# IPSv2_1.net
KiCad netlist of a schematic drawn in EAGLE
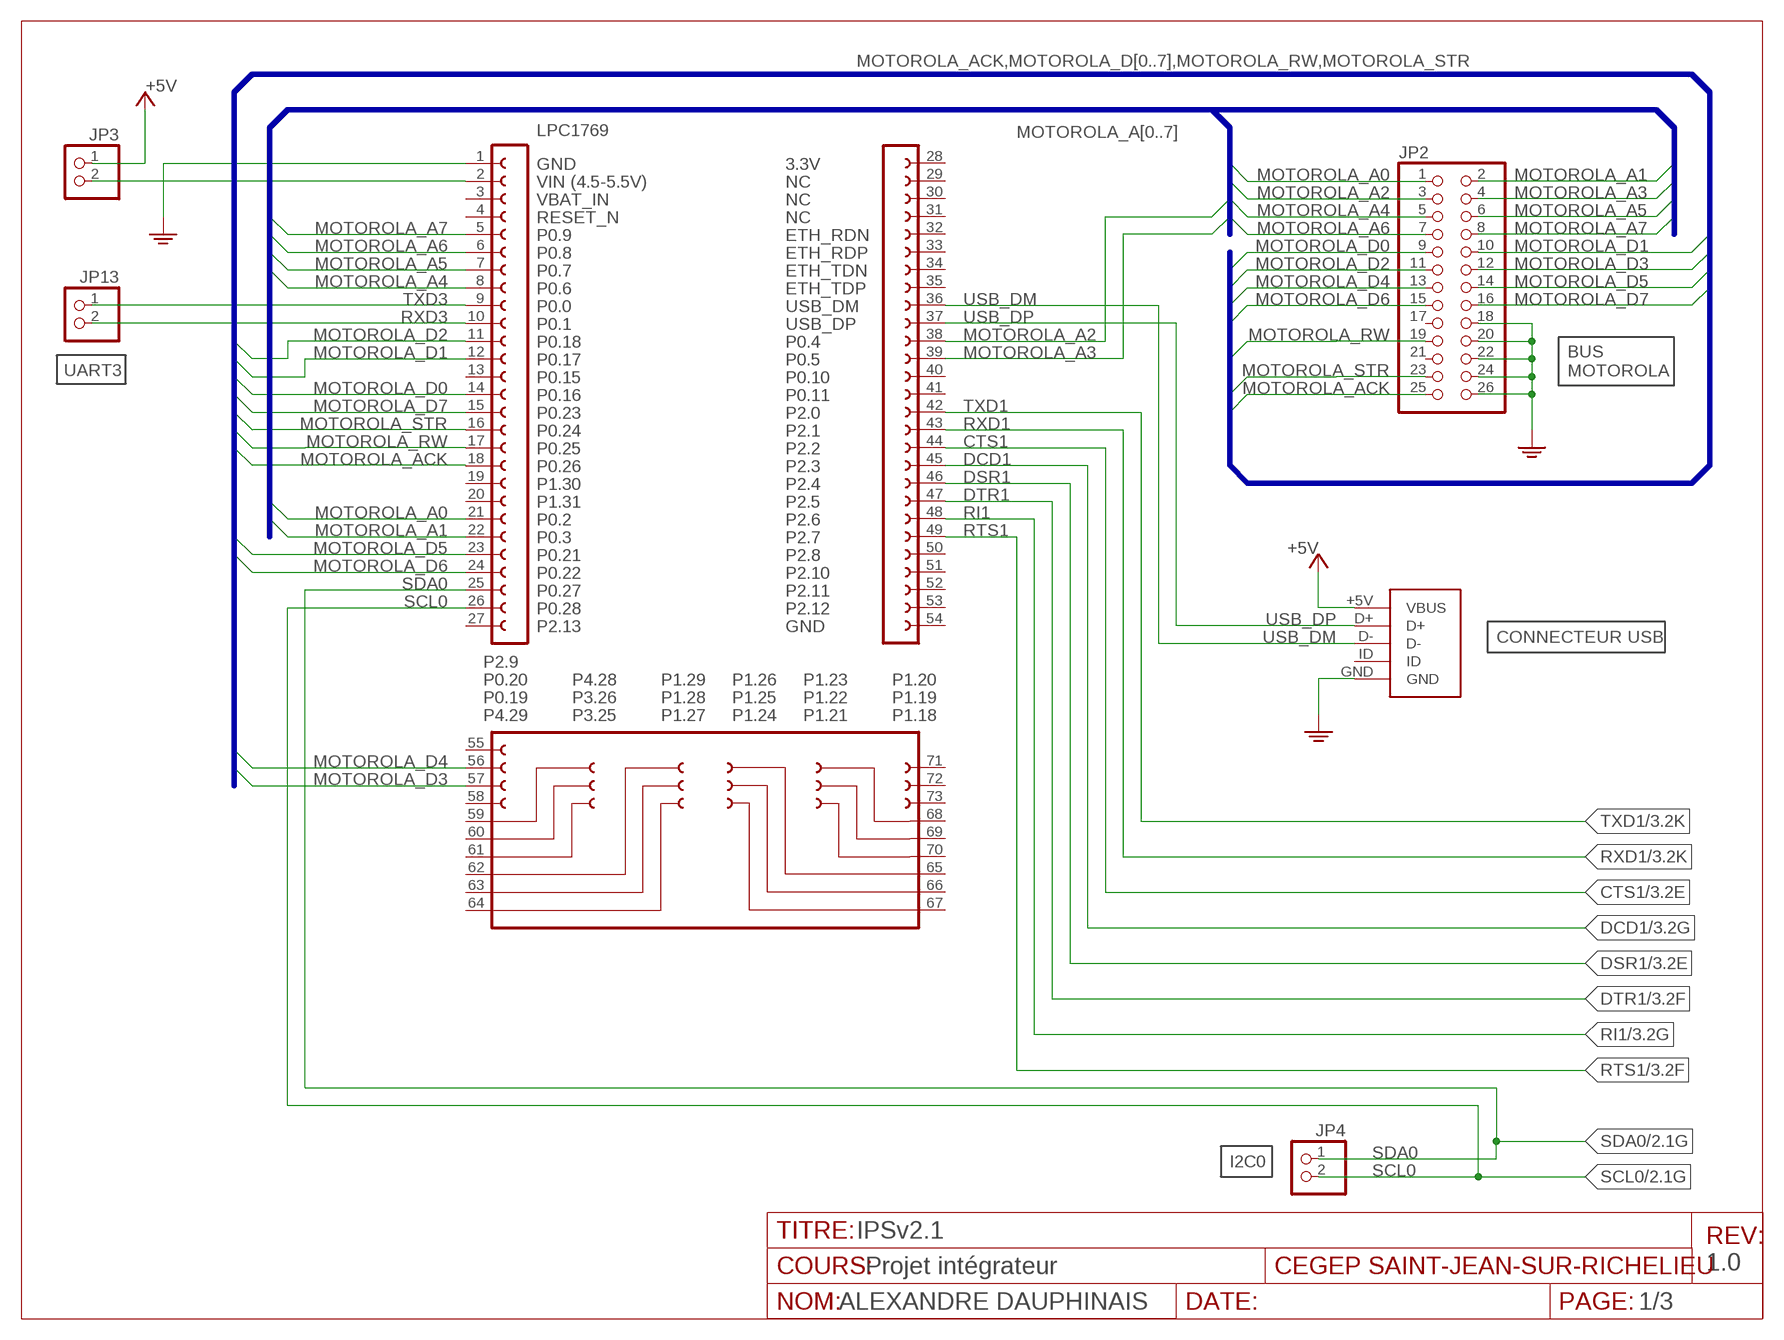
[diagram p0: schematic, sheet 1]
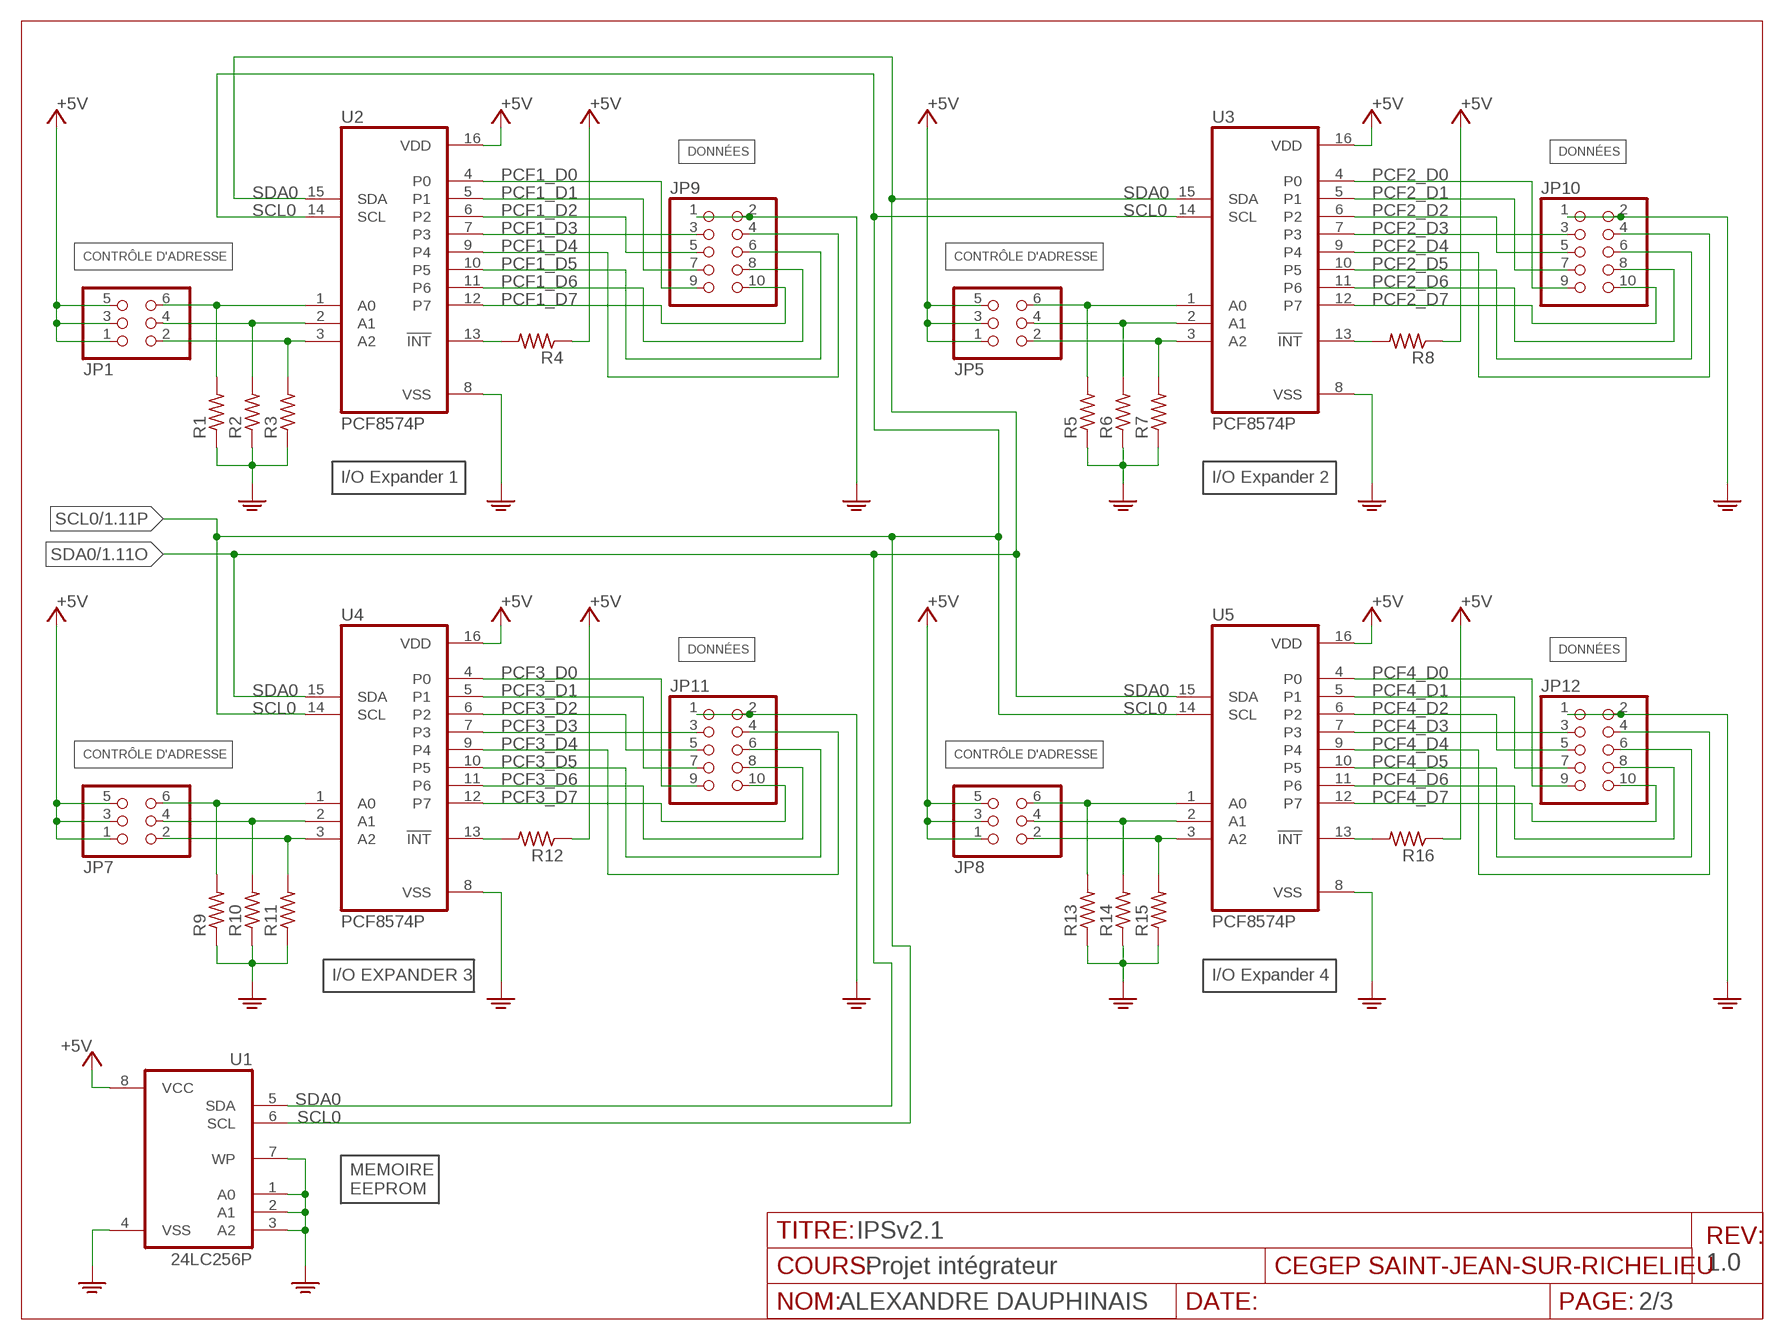
[diagram p1: schematic, sheet 2]
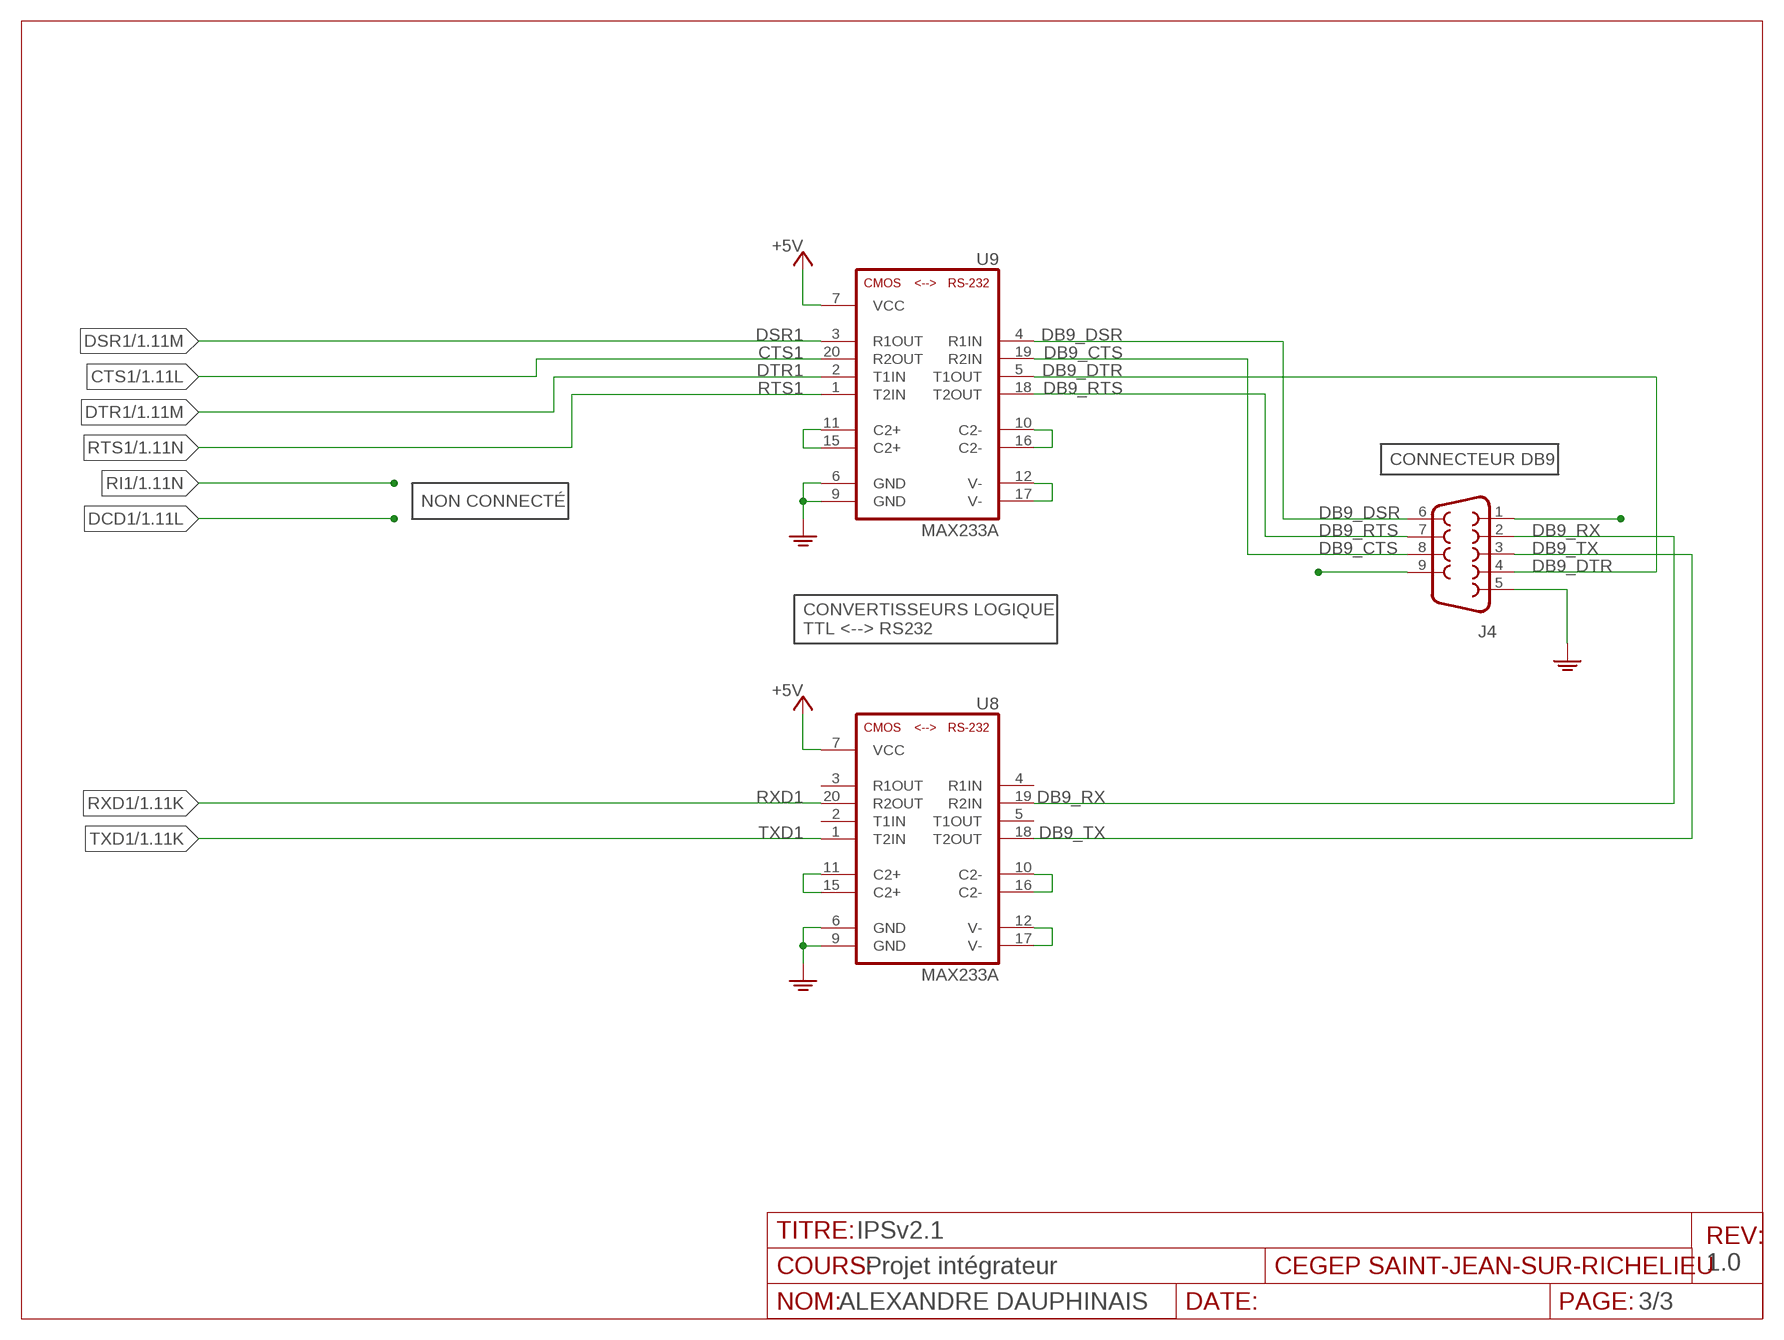
[diagram p2: schematic, sheet 3]

(export (version "E")
  (design (tool "Eeschema 10.0.6"))
  (components
    (comp (ref "J4")
      (value "DB9FEMALE")
      (footprint "eagle-import:DB9")
      (libsource (lib "eagle-import") (part "DB9FEMALE"))
    )
    (comp (ref "U8")
      (value "MAX233A")
      (footprint "eagle-import:DIP20")
      (libsource (lib "eagle-import") (part "MAX233ACPP"))
    )
    (comp (ref "U9")
      (value "MAX233A")
      (footprint "eagle-import:DIP20")
      (libsource (lib "eagle-import") (part "MAX233ACPP"))
    )
    (comp (ref "JP2")
      (value "PINHD-2X13")
      (footprint "eagle-import:2X13")
      (libsource (lib "eagle-import") (part "PINHD-2X13"))
    )
    (comp (ref "JP3")
      (value "PINHD-1X2")
      (footprint "eagle-import:1X02")
      (libsource (lib "eagle-import") (part "PINHD-1X2"))
    )
    (comp (ref "JP4")
      (value "PINHD-1X2")
      (footprint "eagle-import:1X02")
      (libsource (lib "eagle-import") (part "PINHD-1X2"))
    )
    (comp (ref "JP13")
      (value "PINHD-1X2")
      (footprint "eagle-import:1X02")
      (libsource (lib "eagle-import") (part "PINHD-1X2"))
    )
    (comp (ref "LPC1769")
      (value "LPCXPRESSO_LPC1769")
      (footprint "eagle-import:LPCXPRESSO_LPC1769")
      (libsource (lib "eagle-import") (part "LPCXPRESSO_LPC1769"))
    )
    (comp (ref "U$2")
      (value "USB-MICRO-BREAKOUT")
      (footprint "eagle-import:USB-MICRO-BREAKOUT")
      (libsource (lib "eagle-import") (part "USB-MICRO-BREAKOUT"))
    )
    (comp (ref "JP1")
      (value "PINHD-2X3")
      (footprint "eagle-import:2X03")
      (libsource (lib "eagle-import") (part "PINHD-2X3"))
    )
    (comp (ref "JP5")
      (value "PINHD-2X3")
      (footprint "eagle-import:2X03")
      (libsource (lib "eagle-import") (part "PINHD-2X3"))
    )
    (comp (ref "JP7")
      (value "PINHD-2X3")
      (footprint "eagle-import:2X03")
      (libsource (lib "eagle-import") (part "PINHD-2X3"))
    )
    (comp (ref "JP8")
      (value "PINHD-2X3")
      (footprint "eagle-import:2X03")
      (libsource (lib "eagle-import") (part "PINHD-2X3"))
    )
    (comp (ref "JP9")
      (value "PINHD-2X5")
      (footprint "eagle-import:2X05")
      (libsource (lib "eagle-import") (part "PINHD-2X5"))
    )
    (comp (ref "JP10")
      (value "PINHD-2X5")
      (footprint "eagle-import:2X05")
      (libsource (lib "eagle-import") (part "PINHD-2X5"))
    )
    (comp (ref "JP11")
      (value "PINHD-2X5")
      (footprint "eagle-import:2X05")
      (libsource (lib "eagle-import") (part "PINHD-2X5"))
    )
    (comp (ref "JP12")
      (value "PINHD-2X5")
      (footprint "eagle-import:2X05")
      (libsource (lib "eagle-import") (part "PINHD-2X5"))
    )
    (comp (ref "R1")
      (value "R-US_M1206")
      (footprint "eagle-import:M1206")
      (libsource (lib "eagle-import") (part "R-US_M1206"))
    )
    (comp (ref "R2")
      (value "R-US_M1206")
      (footprint "eagle-import:M1206")
      (libsource (lib "eagle-import") (part "R-US_M1206"))
    )
    (comp (ref "R3")
      (value "R-US_M1206")
      (footprint "eagle-import:M1206")
      (libsource (lib "eagle-import") (part "R-US_M1206"))
    )
    (comp (ref "R4")
      (value "R-US_M1206")
      (footprint "eagle-import:M1206")
      (libsource (lib "eagle-import") (part "R-US_M1206"))
    )
    (comp (ref "R5")
      (value "R-US_M1206")
      (footprint "eagle-import:M1206")
      (libsource (lib "eagle-import") (part "R-US_M1206"))
    )
    (comp (ref "R6")
      (value "R-US_M1206")
      (footprint "eagle-import:M1206")
      (libsource (lib "eagle-import") (part "R-US_M1206"))
    )
    (comp (ref "R7")
      (value "R-US_M1206")
      (footprint "eagle-import:M1206")
      (libsource (lib "eagle-import") (part "R-US_M1206"))
    )
    (comp (ref "R8")
      (value "R-US_M1206")
      (footprint "eagle-import:M1206")
      (libsource (lib "eagle-import") (part "R-US_M1206"))
    )
    (comp (ref "R9")
      (value "R-US_M1206")
      (footprint "eagle-import:M1206")
      (libsource (lib "eagle-import") (part "R-US_M1206"))
    )
    (comp (ref "R10")
      (value "R-US_M1206")
      (footprint "eagle-import:M1206")
      (libsource (lib "eagle-import") (part "R-US_M1206"))
    )
    (comp (ref "R11")
      (value "R-US_M1206")
      (footprint "eagle-import:M1206")
      (libsource (lib "eagle-import") (part "R-US_M1206"))
    )
    (comp (ref "R12")
      (value "R-US_M1206")
      (footprint "eagle-import:M1206")
      (libsource (lib "eagle-import") (part "R-US_M1206"))
    )
    (comp (ref "R13")
      (value "R-US_M1206")
      (footprint "eagle-import:M1206")
      (libsource (lib "eagle-import") (part "R-US_M1206"))
    )
    (comp (ref "R14")
      (value "R-US_M1206")
      (footprint "eagle-import:M1206")
      (libsource (lib "eagle-import") (part "R-US_M1206"))
    )
    (comp (ref "R15")
      (value "R-US_M1206")
      (footprint "eagle-import:M1206")
      (libsource (lib "eagle-import") (part "R-US_M1206"))
    )
    (comp (ref "R16")
      (value "R-US_M1206")
      (footprint "eagle-import:M1206")
      (libsource (lib "eagle-import") (part "R-US_M1206"))
    )
    (comp (ref "U1")
      (value "24LC256P")
      (footprint "eagle-import:DIP08")
      (libsource (lib "eagle-import") (part "24LC256P"))
    )
    (comp (ref "U2")
      (value "PCF8574P")
      (footprint "eagle-import:DIP16")
      (libsource (lib "eagle-import") (part "PCF8574P"))
    )
    (comp (ref "U3")
      (value "PCF8574P")
      (footprint "eagle-import:DIP16")
      (libsource (lib "eagle-import") (part "PCF8574P"))
    )
    (comp (ref "U4")
      (value "PCF8574P")
      (footprint "eagle-import:DIP16")
      (libsource (lib "eagle-import") (part "PCF8574P"))
    )
    (comp (ref "U5")
      (value "PCF8574P")
      (footprint "eagle-import:DIP16")
      (libsource (lib "eagle-import") (part "PCF8574P"))
    )
  )
  (nets
    (net (code "1") (name "+5V") (class "Default")
      (node (ref "JP1") (pin "1") (pinfunction "1_1") (pintype "passive"))
      (node (ref "JP1") (pin "3") (pinfunction "3_3") (pintype "passive"))
      (node (ref "JP1") (pin "5") (pinfunction "5_5") (pintype "passive"))
      (node (ref "JP3") (pin "1") (pinfunction "1_1") (pintype "passive"))
      (node (ref "JP5") (pin "1") (pinfunction "1_1") (pintype "passive"))
      (node (ref "JP5") (pin "3") (pinfunction "3_3") (pintype "passive"))
      (node (ref "JP5") (pin "5") (pinfunction "5_5") (pintype "passive"))
      (node (ref "JP7") (pin "1") (pinfunction "1_1") (pintype "passive"))
      (node (ref "JP7") (pin "3") (pinfunction "3_3") (pintype "passive"))
      (node (ref "JP7") (pin "5") (pinfunction "5_5") (pintype "passive"))
      (node (ref "JP8") (pin "1") (pinfunction "1_1") (pintype "passive"))
      (node (ref "JP8") (pin "3") (pinfunction "3_3") (pintype "passive"))
      (node (ref "JP8") (pin "5") (pinfunction "5_5") (pintype "passive"))
      (node (ref "R12") (pin "1") (pinfunction "1_1") (pintype "passive"))
      (node (ref "R16") (pin "1") (pinfunction "1_1") (pintype "passive"))
      (node (ref "R4") (pin "1") (pinfunction "1_1") (pintype "passive"))
      (node (ref "R8") (pin "1") (pinfunction "1_1") (pintype "passive"))
      (node (ref "U$2") (pin "+5V") (pinfunction "VBUS_+5V") (pintype "power_in"))
      (node (ref "U1") (pin "8") (pinfunction "VCC_8") (pintype "power_in"))
      (node (ref "U2") (pin "16") (pinfunction "VDD_16") (pintype "power_in"))
      (node (ref "U3") (pin "16") (pinfunction "VDD_16") (pintype "power_in"))
      (node (ref "U4") (pin "16") (pinfunction "VDD_16") (pintype "power_in"))
      (node (ref "U5") (pin "16") (pinfunction "VDD_16") (pintype "power_in"))
      (node (ref "U8") (pin "7") (pinfunction "VCC_7") (pintype "power_in"))
      (node (ref "U9") (pin "7") (pinfunction "VCC_7") (pintype "power_in"))
    )
    (net (code "4") (name "CTS1") (class "Default")
      (node (ref "LPC1769") (pin "44") (pinfunction "44_44") (pintype "passive"))
      (node (ref "U9") (pin "20") (pinfunction "R2OUT_20") (pintype "output"))
    )
    (net (code "5") (name "DB9_CTS") (class "Default")
      (node (ref "J4") (pin "8") (pinfunction "8_8") (pintype "passive"))
      (node (ref "U9") (pin "19") (pinfunction "R2IN_19") (pintype "input"))
    )
    (net (code "6") (name "DB9_DSR") (class "Default")
      (node (ref "J4") (pin "6") (pinfunction "6_6") (pintype "passive"))
      (node (ref "U9") (pin "4") (pinfunction "R1IN_4") (pintype "input"))
    )
    (net (code "7") (name "DB9_DTR") (class "Default")
      (node (ref "J4") (pin "4") (pinfunction "4_4") (pintype "passive"))
      (node (ref "U9") (pin "5") (pinfunction "T1OUT_5") (pintype "output"))
    )
    (net (code "8") (name "DB9_RTS") (class "Default")
      (node (ref "J4") (pin "7") (pinfunction "7_7") (pintype "passive"))
      (node (ref "U9") (pin "18") (pinfunction "T2OUT_18") (pintype "output"))
    )
    (net (code "9") (name "DB9_RX") (class "Default")
      (node (ref "J4") (pin "2") (pinfunction "2_2") (pintype "passive"))
      (node (ref "U8") (pin "19") (pinfunction "R2IN_19") (pintype "input"))
    )
    (net (code "10") (name "DB9_TX") (class "Default")
      (node (ref "J4") (pin "3") (pinfunction "3_3") (pintype "passive"))
      (node (ref "U8") (pin "18") (pinfunction "T2OUT_18") (pintype "output"))
    )
    (net (code "11") (name "DCD1") (class "Default")
      (node (ref "LPC1769") (pin "45") (pinfunction "45_45") (pintype "passive"))
    )
    (net (code "12") (name "DSR1") (class "Default")
      (node (ref "LPC1769") (pin "46") (pinfunction "46_46") (pintype "passive"))
      (node (ref "U9") (pin "3") (pinfunction "R1OUT_3") (pintype "output"))
    )
    (net (code "13") (name "DTR1") (class "Default")
      (node (ref "LPC1769") (pin "47") (pinfunction "47_47") (pintype "passive"))
      (node (ref "U9") (pin "2") (pinfunction "T1IN_2") (pintype "input"))
    )
    (net (code "14") (name "GND") (class "Default")
      (node (ref "J4") (pin "5") (pinfunction "5_5") (pintype "passive"))
      (node (ref "JP10") (pin "1") (pinfunction "1_1") (pintype "passive"))
      (node (ref "JP10") (pin "2") (pinfunction "2_2") (pintype "passive"))
      (node (ref "JP11") (pin "1") (pinfunction "1_1") (pintype "passive"))
      (node (ref "JP11") (pin "2") (pinfunction "2_2") (pintype "passive"))
      (node (ref "JP12") (pin "1") (pinfunction "1_1") (pintype "passive"))
      (node (ref "JP12") (pin "2") (pinfunction "2_2") (pintype "passive"))
      (node (ref "JP2") (pin "18") (pinfunction "18_18") (pintype "passive"))
      (node (ref "JP2") (pin "20") (pinfunction "20_20") (pintype "passive"))
      (node (ref "JP2") (pin "22") (pinfunction "22_22") (pintype "passive"))
      (node (ref "JP2") (pin "24") (pinfunction "24_24") (pintype "passive"))
      (node (ref "JP2") (pin "26") (pinfunction "26_26") (pintype "passive"))
      (node (ref "JP9") (pin "1") (pinfunction "1_1") (pintype "passive"))
      (node (ref "JP9") (pin "2") (pinfunction "2_2") (pintype "passive"))
      (node (ref "LPC1769") (pin "1") (pinfunction "1_1") (pintype "passive"))
      (node (ref "R1") (pin "1") (pinfunction "1_1") (pintype "passive"))
      (node (ref "R10") (pin "1") (pinfunction "1_1") (pintype "passive"))
      (node (ref "R11") (pin "1") (pinfunction "1_1") (pintype "passive"))
      (node (ref "R13") (pin "1") (pinfunction "1_1") (pintype "passive"))
      (node (ref "R14") (pin "1") (pinfunction "1_1") (pintype "passive"))
      (node (ref "R15") (pin "1") (pinfunction "1_1") (pintype "passive"))
      (node (ref "R2") (pin "1") (pinfunction "1_1") (pintype "passive"))
      (node (ref "R3") (pin "1") (pinfunction "1_1") (pintype "passive"))
      (node (ref "R5") (pin "1") (pinfunction "1_1") (pintype "passive"))
      (node (ref "R6") (pin "1") (pinfunction "1_1") (pintype "passive"))
      (node (ref "R7") (pin "1") (pinfunction "1_1") (pintype "passive"))
      (node (ref "R9") (pin "1") (pinfunction "1_1") (pintype "passive"))
      (node (ref "U$2") (pin "GND") (pinfunction "GND_GND") (pintype "power_in"))
      (node (ref "U1") (pin "1") (pinfunction "A0_1") (pintype "input"))
      (node (ref "U1") (pin "2") (pinfunction "A1_2") (pintype "input"))
      (node (ref "U1") (pin "3") (pinfunction "A2_3") (pintype "input"))
      (node (ref "U1") (pin "4") (pinfunction "VSS_4") (pintype "power_in"))
      (node (ref "U1") (pin "7") (pinfunction "WP_7") (pintype "input"))
      (node (ref "U2") (pin "8") (pinfunction "VSS_8") (pintype "power_in"))
      (node (ref "U3") (pin "8") (pinfunction "VSS_8") (pintype "power_in"))
      (node (ref "U4") (pin "8") (pinfunction "VSS_8") (pintype "power_in"))
      (node (ref "U5") (pin "8") (pinfunction "VSS_8") (pintype "power_in"))
      (node (ref "U8") (pin "6") (pinfunction "GND_6") (pintype "power_in"))
      (node (ref "U8") (pin "9") (pinfunction "GND_9") (pintype "power_in"))
      (node (ref "U9") (pin "6") (pinfunction "GND_6") (pintype "power_in"))
      (node (ref "U9") (pin "9") (pinfunction "GND_9") (pintype "power_in"))
    )
    (net (code "15") (name "MOTOROLA_A0") (class "Default")
      (node (ref "JP2") (pin "1") (pinfunction "1_1") (pintype "passive"))
      (node (ref "LPC1769") (pin "21") (pinfunction "21_21") (pintype "passive"))
    )
    (net (code "16") (name "MOTOROLA_A1") (class "Default")
      (node (ref "JP2") (pin "2") (pinfunction "2_2") (pintype "passive"))
      (node (ref "LPC1769") (pin "22") (pinfunction "22_22") (pintype "passive"))
    )
    (net (code "17") (name "MOTOROLA_A2") (class "Default")
      (node (ref "JP2") (pin "3") (pinfunction "3_3") (pintype "passive"))
      (node (ref "LPC1769") (pin "38") (pinfunction "38_38") (pintype "passive"))
    )
    (net (code "18") (name "MOTOROLA_A3") (class "Default")
      (node (ref "JP2") (pin "4") (pinfunction "4_4") (pintype "passive"))
      (node (ref "LPC1769") (pin "39") (pinfunction "39_39") (pintype "passive"))
    )
    (net (code "19") (name "MOTOROLA_A4") (class "Default")
      (node (ref "JP2") (pin "5") (pinfunction "5_5") (pintype "passive"))
      (node (ref "LPC1769") (pin "8") (pinfunction "8_8") (pintype "passive"))
    )
    (net (code "20") (name "MOTOROLA_A5") (class "Default")
      (node (ref "JP2") (pin "6") (pinfunction "6_6") (pintype "passive"))
      (node (ref "LPC1769") (pin "7") (pinfunction "7_7") (pintype "passive"))
    )
    (net (code "21") (name "MOTOROLA_A6") (class "Default")
      (node (ref "JP2") (pin "7") (pinfunction "7_7") (pintype "passive"))
      (node (ref "LPC1769") (pin "6") (pinfunction "6_6") (pintype "passive"))
    )
    (net (code "22") (name "MOTOROLA_A7") (class "Default")
      (node (ref "JP2") (pin "8") (pinfunction "8_8") (pintype "passive"))
      (node (ref "LPC1769") (pin "5") (pinfunction "5_5") (pintype "passive"))
    )
    (net (code "23") (name "MOTOROLA_ACK") (class "Default")
      (node (ref "JP2") (pin "25") (pinfunction "25_25") (pintype "passive"))
      (node (ref "LPC1769") (pin "18") (pinfunction "18_18") (pintype "passive"))
    )
    (net (code "24") (name "MOTOROLA_D0") (class "Default")
      (node (ref "JP2") (pin "9") (pinfunction "9_9") (pintype "passive"))
      (node (ref "LPC1769") (pin "14") (pinfunction "14_14") (pintype "passive"))
    )
    (net (code "25") (name "MOTOROLA_D1") (class "Default")
      (node (ref "JP2") (pin "10") (pinfunction "10_10") (pintype "passive"))
      (node (ref "LPC1769") (pin "12") (pinfunction "12_12") (pintype "passive"))
    )
    (net (code "26") (name "MOTOROLA_D2") (class "Default")
      (node (ref "JP2") (pin "11") (pinfunction "11_11") (pintype "passive"))
      (node (ref "LPC1769") (pin "11") (pinfunction "11_11") (pintype "passive"))
    )
    (net (code "27") (name "MOTOROLA_D3") (class "Default")
      (node (ref "JP2") (pin "12") (pinfunction "12_12") (pintype "passive"))
      (node (ref "LPC1769") (pin "57") (pinfunction "57_57") (pintype "passive"))
    )
    (net (code "28") (name "MOTOROLA_D4") (class "Default")
      (node (ref "JP2") (pin "13") (pinfunction "13_13") (pintype "passive"))
      (node (ref "LPC1769") (pin "56") (pinfunction "56_56") (pintype "passive"))
    )
    (net (code "29") (name "MOTOROLA_D5") (class "Default")
      (node (ref "JP2") (pin "14") (pinfunction "14_14") (pintype "passive"))
      (node (ref "LPC1769") (pin "23") (pinfunction "23_23") (pintype "passive"))
    )
    (net (code "30") (name "MOTOROLA_D6") (class "Default")
      (node (ref "JP2") (pin "15") (pinfunction "15_15") (pintype "passive"))
      (node (ref "LPC1769") (pin "24") (pinfunction "24_24") (pintype "passive"))
    )
    (net (code "31") (name "MOTOROLA_D7") (class "Default")
      (node (ref "JP2") (pin "16") (pinfunction "16_16") (pintype "passive"))
      (node (ref "LPC1769") (pin "15") (pinfunction "15_15") (pintype "passive"))
    )
    (net (code "32") (name "MOTOROLA_RW") (class "Default")
      (node (ref "JP2") (pin "19") (pinfunction "19_19") (pintype "passive"))
      (node (ref "LPC1769") (pin "17") (pinfunction "17_17") (pintype "passive"))
    )
    (net (code "33") (name "MOTOROLA_STR") (class "Default")
      (node (ref "JP2") (pin "23") (pinfunction "23_23") (pintype "passive"))
      (node (ref "LPC1769") (pin "16") (pinfunction "16_16") (pintype "passive"))
    )
    (net (code "34") (name "Net-(JP3-Pad2)") (class "Default")
      (node (ref "JP3") (pin "2") (pinfunction "2_2") (pintype "passive"))
      (node (ref "LPC1769") (pin "2") (pinfunction "2_2") (pintype "passive"))
    )
    (net (code "35") (name "Net-(U2-A0)") (class "Default")
      (node (ref "JP1") (pin "6") (pinfunction "6_6") (pintype "passive"))
      (node (ref "R1") (pin "2") (pinfunction "2_2") (pintype "passive"))
      (node (ref "U2") (pin "1") (pinfunction "A0_1") (pintype "input"))
    )
    (net (code "36") (name "Net-(U2-A1)") (class "Default")
      (node (ref "JP1") (pin "4") (pinfunction "4_4") (pintype "passive"))
      (node (ref "R2") (pin "2") (pinfunction "2_2") (pintype "passive"))
      (node (ref "U2") (pin "2") (pinfunction "A1_2") (pintype "input"))
    )
    (net (code "37") (name "Net-(U2-A2)") (class "Default")
      (node (ref "JP1") (pin "2") (pinfunction "2_2") (pintype "passive"))
      (node (ref "R3") (pin "2") (pinfunction "2_2") (pintype "passive"))
      (node (ref "U2") (pin "3") (pinfunction "A2_3") (pintype "input"))
    )
    (net (code "38") (name "Net-(U2-~{INT})") (class "Default")
      (node (ref "R4") (pin "2") (pinfunction "2_2") (pintype "passive"))
      (node (ref "U2") (pin "13") (pinfunction "~{INT}_13") (pintype "output"))
    )
    (net (code "39") (name "Net-(U3-A0)") (class "Default")
      (node (ref "JP5") (pin "6") (pinfunction "6_6") (pintype "passive"))
      (node (ref "R5") (pin "2") (pinfunction "2_2") (pintype "passive"))
      (node (ref "U3") (pin "1") (pinfunction "A0_1") (pintype "input"))
    )
    (net (code "40") (name "Net-(U3-A1)") (class "Default")
      (node (ref "JP5") (pin "4") (pinfunction "4_4") (pintype "passive"))
      (node (ref "R6") (pin "2") (pinfunction "2_2") (pintype "passive"))
      (node (ref "U3") (pin "2") (pinfunction "A1_2") (pintype "input"))
    )
    (net (code "41") (name "Net-(U3-A2)") (class "Default")
      (node (ref "JP5") (pin "2") (pinfunction "2_2") (pintype "passive"))
      (node (ref "R7") (pin "2") (pinfunction "2_2") (pintype "passive"))
      (node (ref "U3") (pin "3") (pinfunction "A2_3") (pintype "input"))
    )
    (net (code "42") (name "Net-(U3-~{INT})") (class "Default")
      (node (ref "R8") (pin "2") (pinfunction "2_2") (pintype "passive"))
      (node (ref "U3") (pin "13") (pinfunction "~{INT}_13") (pintype "output"))
    )
    (net (code "43") (name "Net-(U4-A0)") (class "Default")
      (node (ref "JP7") (pin "6") (pinfunction "6_6") (pintype "passive"))
      (node (ref "R9") (pin "2") (pinfunction "2_2") (pintype "passive"))
      (node (ref "U4") (pin "1") (pinfunction "A0_1") (pintype "input"))
    )
    (net (code "44") (name "Net-(U4-A1)") (class "Default")
      (node (ref "JP7") (pin "4") (pinfunction "4_4") (pintype "passive"))
      (node (ref "R10") (pin "2") (pinfunction "2_2") (pintype "passive"))
      (node (ref "U4") (pin "2") (pinfunction "A1_2") (pintype "input"))
    )
    (net (code "45") (name "Net-(U4-A2)") (class "Default")
      (node (ref "JP7") (pin "2") (pinfunction "2_2") (pintype "passive"))
      (node (ref "R11") (pin "2") (pinfunction "2_2") (pintype "passive"))
      (node (ref "U4") (pin "3") (pinfunction "A2_3") (pintype "input"))
    )
    (net (code "46") (name "Net-(U4-~{INT})") (class "Default")
      (node (ref "R12") (pin "2") (pinfunction "2_2") (pintype "passive"))
      (node (ref "U4") (pin "13") (pinfunction "~{INT}_13") (pintype "output"))
    )
    (net (code "47") (name "Net-(U5-A0)") (class "Default")
      (node (ref "JP8") (pin "6") (pinfunction "6_6") (pintype "passive"))
      (node (ref "R13") (pin "2") (pinfunction "2_2") (pintype "passive"))
      (node (ref "U5") (pin "1") (pinfunction "A0_1") (pintype "input"))
    )
    (net (code "48") (name "Net-(U5-A1)") (class "Default")
      (node (ref "JP8") (pin "4") (pinfunction "4_4") (pintype "passive"))
      (node (ref "R14") (pin "2") (pinfunction "2_2") (pintype "passive"))
      (node (ref "U5") (pin "2") (pinfunction "A1_2") (pintype "input"))
    )
    (net (code "49") (name "Net-(U5-A2)") (class "Default")
      (node (ref "JP8") (pin "2") (pinfunction "2_2") (pintype "passive"))
      (node (ref "R15") (pin "2") (pinfunction "2_2") (pintype "passive"))
      (node (ref "U5") (pin "3") (pinfunction "A2_3") (pintype "input"))
    )
    (net (code "50") (name "Net-(U5-~{INT})") (class "Default")
      (node (ref "R16") (pin "2") (pinfunction "2_2") (pintype "passive"))
      (node (ref "U5") (pin "13") (pinfunction "~{INT}_13") (pintype "output"))
    )
    (net (code "51") (name "Net-(U8-C2+-Pad11)") (class "Default")
      (node (ref "U8") (pin "11") (pinfunction "C2+_11") (pintype "passive"))
      (node (ref "U8") (pin "15") (pinfunction "C2+_15") (pintype "passive"))
    )
    (net (code "52") (name "Net-(U8-C2--Pad10)") (class "Default")
      (node (ref "U8") (pin "10") (pinfunction "C2-_10") (pintype "passive"))
      (node (ref "U8") (pin "16") (pinfunction "C2-_16") (pintype "passive"))
    )
    (net (code "53") (name "Net-(U8-V--Pad12)") (class "Default")
      (node (ref "U8") (pin "12") (pinfunction "V-_12") (pintype "passive"))
      (node (ref "U8") (pin "17") (pinfunction "V-_17") (pintype "passive"))
    )
    (net (code "54") (name "Net-(U9-C2+-Pad11)") (class "Default")
      (node (ref "U9") (pin "11") (pinfunction "C2+_11") (pintype "passive"))
      (node (ref "U9") (pin "15") (pinfunction "C2+_15") (pintype "passive"))
    )
    (net (code "55") (name "Net-(U9-C2--Pad10)") (class "Default")
      (node (ref "U9") (pin "10") (pinfunction "C2-_10") (pintype "passive"))
      (node (ref "U9") (pin "16") (pinfunction "C2-_16") (pintype "passive"))
    )
    (net (code "56") (name "Net-(U9-V--Pad12)") (class "Default")
      (node (ref "U9") (pin "12") (pinfunction "V-_12") (pintype "passive"))
      (node (ref "U9") (pin "17") (pinfunction "V-_17") (pintype "passive"))
    )
    (net (code "57") (name "PCF1_D0") (class "Default")
      (node (ref "JP9") (pin "9") (pinfunction "9_9") (pintype "passive"))
      (node (ref "U2") (pin "4") (pinfunction "P0_4") (pintype "bidirectional"))
    )
    (net (code "58") (name "PCF1_D1") (class "Default")
      (node (ref "JP9") (pin "7") (pinfunction "7_7") (pintype "passive"))
      (node (ref "U2") (pin "5") (pinfunction "P1_5") (pintype "bidirectional"))
    )
    (net (code "59") (name "PCF1_D2") (class "Default")
      (node (ref "JP9") (pin "5") (pinfunction "5_5") (pintype "passive"))
      (node (ref "U2") (pin "6") (pinfunction "P2_6") (pintype "bidirectional"))
    )
    (net (code "60") (name "PCF1_D3") (class "Default")
      (node (ref "JP9") (pin "3") (pinfunction "3_3") (pintype "passive"))
      (node (ref "U2") (pin "7") (pinfunction "P3_7") (pintype "bidirectional"))
    )
    (net (code "61") (name "PCF1_D4") (class "Default")
      (node (ref "JP9") (pin "4") (pinfunction "4_4") (pintype "passive"))
      (node (ref "U2") (pin "9") (pinfunction "P4_9") (pintype "bidirectional"))
    )
    (net (code "62") (name "PCF1_D5") (class "Default")
      (node (ref "JP9") (pin "6") (pinfunction "6_6") (pintype "passive"))
      (node (ref "U2") (pin "10") (pinfunction "P5_10") (pintype "bidirectional"))
    )
    (net (code "63") (name "PCF1_D6") (class "Default")
      (node (ref "JP9") (pin "8") (pinfunction "8_8") (pintype "passive"))
      (node (ref "U2") (pin "11") (pinfunction "P6_11") (pintype "bidirectional"))
    )
    (net (code "64") (name "PCF1_D7") (class "Default")
      (node (ref "JP9") (pin "10") (pinfunction "10_10") (pintype "passive"))
      (node (ref "U2") (pin "12") (pinfunction "P7_12") (pintype "bidirectional"))
    )
    (net (code "65") (name "PCF2_D0") (class "Default")
      (node (ref "JP10") (pin "9") (pinfunction "9_9") (pintype "passive"))
      (node (ref "U3") (pin "4") (pinfunction "P0_4") (pintype "bidirectional"))
    )
    (net (code "66") (name "PCF2_D1") (class "Default")
      (node (ref "JP10") (pin "7") (pinfunction "7_7") (pintype "passive"))
      (node (ref "U3") (pin "5") (pinfunction "P1_5") (pintype "bidirectional"))
    )
    (net (code "67") (name "PCF2_D2") (class "Default")
      (node (ref "JP10") (pin "5") (pinfunction "5_5") (pintype "passive"))
      (node (ref "U3") (pin "6") (pinfunction "P2_6") (pintype "bidirectional"))
    )
    (net (code "68") (name "PCF2_D3") (class "Default")
      (node (ref "JP10") (pin "3") (pinfunction "3_3") (pintype "passive"))
      (node (ref "U3") (pin "7") (pinfunction "P3_7") (pintype "bidirectional"))
    )
    (net (code "69") (name "PCF2_D4") (class "Default")
      (node (ref "JP10") (pin "4") (pinfunction "4_4") (pintype "passive"))
      (node (ref "U3") (pin "9") (pinfunction "P4_9") (pintype "bidirectional"))
    )
    (net (code "70") (name "PCF2_D5") (class "Default")
      (node (ref "JP10") (pin "6") (pinfunction "6_6") (pintype "passive"))
      (node (ref "U3") (pin "10") (pinfunction "P5_10") (pintype "bidirectional"))
    )
    (net (code "71") (name "PCF2_D6") (class "Default")
      (node (ref "JP10") (pin "8") (pinfunction "8_8") (pintype "passive"))
      (node (ref "U3") (pin "11") (pinfunction "P6_11") (pintype "bidirectional"))
    )
    (net (code "72") (name "PCF2_D7") (class "Default")
      (node (ref "JP10") (pin "10") (pinfunction "10_10") (pintype "passive"))
      (node (ref "U3") (pin "12") (pinfunction "P7_12") (pintype "bidirectional"))
    )
    (net (code "73") (name "PCF3_D0") (class "Default")
      (node (ref "JP11") (pin "9") (pinfunction "9_9") (pintype "passive"))
      (node (ref "U4") (pin "4") (pinfunction "P0_4") (pintype "bidirectional"))
    )
    (net (code "74") (name "PCF3_D1") (class "Default")
      (node (ref "JP11") (pin "7") (pinfunction "7_7") (pintype "passive"))
      (node (ref "U4") (pin "5") (pinfunction "P1_5") (pintype "bidirectional"))
    )
    (net (code "75") (name "PCF3_D2") (class "Default")
      (node (ref "JP11") (pin "5") (pinfunction "5_5") (pintype "passive"))
      (node (ref "U4") (pin "6") (pinfunction "P2_6") (pintype "bidirectional"))
    )
    (net (code "76") (name "PCF3_D3") (class "Default")
      (node (ref "JP11") (pin "3") (pinfunction "3_3") (pintype "passive"))
      (node (ref "U4") (pin "7") (pinfunction "P3_7") (pintype "bidirectional"))
    )
    (net (code "77") (name "PCF3_D4") (class "Default")
      (node (ref "JP11") (pin "4") (pinfunction "4_4") (pintype "passive"))
      (node (ref "U4") (pin "9") (pinfunction "P4_9") (pintype "bidirectional"))
    )
    (net (code "78") (name "PCF3_D5") (class "Default")
      (node (ref "JP11") (pin "6") (pinfunction "6_6") (pintype "passive"))
      (node (ref "U4") (pin "10") (pinfunction "P5_10") (pintype "bidirectional"))
    )
    (net (code "79") (name "PCF3_D6") (class "Default")
      (node (ref "JP11") (pin "8") (pinfunction "8_8") (pintype "passive"))
      (node (ref "U4") (pin "11") (pinfunction "P6_11") (pintype "bidirectional"))
    )
    (net (code "80") (name "PCF3_D7") (class "Default")
      (node (ref "JP11") (pin "10") (pinfunction "10_10") (pintype "passive"))
      (node (ref "U4") (pin "12") (pinfunction "P7_12") (pintype "bidirectional"))
    )
    (net (code "81") (name "PCF4_D0") (class "Default")
      (node (ref "JP12") (pin "9") (pinfunction "9_9") (pintype "passive"))
      (node (ref "U5") (pin "4") (pinfunction "P0_4") (pintype "bidirectional"))
    )
    (net (code "82") (name "PCF4_D1") (class "Default")
      (node (ref "JP12") (pin "7") (pinfunction "7_7") (pintype "passive"))
      (node (ref "U5") (pin "5") (pinfunction "P1_5") (pintype "bidirectional"))
    )
    (net (code "83") (name "PCF4_D2") (class "Default")
      (node (ref "JP12") (pin "5") (pinfunction "5_5") (pintype "passive"))
      (node (ref "U5") (pin "6") (pinfunction "P2_6") (pintype "bidirectional"))
    )
    (net (code "84") (name "PCF4_D3") (class "Default")
      (node (ref "JP12") (pin "3") (pinfunction "3_3") (pintype "passive"))
      (node (ref "U5") (pin "7") (pinfunction "P3_7") (pintype "bidirectional"))
    )
    (net (code "85") (name "PCF4_D4") (class "Default")
      (node (ref "JP12") (pin "4") (pinfunction "4_4") (pintype "passive"))
      (node (ref "U5") (pin "9") (pinfunction "P4_9") (pintype "bidirectional"))
    )
    (net (code "86") (name "PCF4_D5") (class "Default")
      (node (ref "JP12") (pin "6") (pinfunction "6_6") (pintype "passive"))
      (node (ref "U5") (pin "10") (pinfunction "P5_10") (pintype "bidirectional"))
    )
    (net (code "87") (name "PCF4_D6") (class "Default")
      (node (ref "JP12") (pin "8") (pinfunction "8_8") (pintype "passive"))
      (node (ref "U5") (pin "11") (pinfunction "P6_11") (pintype "bidirectional"))
    )
    (net (code "88") (name "PCF4_D7") (class "Default")
      (node (ref "JP12") (pin "10") (pinfunction "10_10") (pintype "passive"))
      (node (ref "U5") (pin "12") (pinfunction "P7_12") (pintype "bidirectional"))
    )
    (net (code "89") (name "RI1") (class "Default")
      (node (ref "LPC1769") (pin "48") (pinfunction "48_48") (pintype "passive"))
    )
    (net (code "90") (name "RTS1") (class "Default")
      (node (ref "LPC1769") (pin "49") (pinfunction "49_49") (pintype "passive"))
      (node (ref "U9") (pin "1") (pinfunction "T2IN_1") (pintype "input"))
    )
    (net (code "91") (name "RXD1") (class "Default")
      (node (ref "LPC1769") (pin "43") (pinfunction "43_43") (pintype "passive"))
      (node (ref "U8") (pin "20") (pinfunction "R2OUT_20") (pintype "output"))
    )
    (net (code "92") (name "RXD3") (class "Default")
      (node (ref "JP13") (pin "2") (pinfunction "2_2") (pintype "passive"))
      (node (ref "LPC1769") (pin "10") (pinfunction "10_10") (pintype "passive"))
    )
    (net (code "93") (name "SCL0") (class "Default")
      (node (ref "JP4") (pin "2") (pinfunction "2_2") (pintype "passive"))
      (node (ref "LPC1769") (pin "26") (pinfunction "26_26") (pintype "passive"))
      (node (ref "U1") (pin "6") (pinfunction "SCL_6") (pintype "input"))
      (node (ref "U2") (pin "14") (pinfunction "SCL_14") (pintype "input"))
      (node (ref "U3") (pin "14") (pinfunction "SCL_14") (pintype "input"))
      (node (ref "U4") (pin "14") (pinfunction "SCL_14") (pintype "input"))
      (node (ref "U5") (pin "14") (pinfunction "SCL_14") (pintype "input"))
    )
    (net (code "94") (name "SDA0") (class "Default")
      (node (ref "JP4") (pin "1") (pinfunction "1_1") (pintype "passive"))
      (node (ref "LPC1769") (pin "25") (pinfunction "25_25") (pintype "passive"))
      (node (ref "U1") (pin "5") (pinfunction "SDA_5") (pintype "bidirectional"))
      (node (ref "U2") (pin "15") (pinfunction "SDA_15") (pintype "bidirectional"))
      (node (ref "U3") (pin "15") (pinfunction "SDA_15") (pintype "bidirectional"))
      (node (ref "U4") (pin "15") (pinfunction "SDA_15") (pintype "bidirectional"))
      (node (ref "U5") (pin "15") (pinfunction "SDA_15") (pintype "bidirectional"))
    )
    (net (code "95") (name "TXD1") (class "Default")
      (node (ref "LPC1769") (pin "42") (pinfunction "42_42") (pintype "passive"))
      (node (ref "U8") (pin "1") (pinfunction "T2IN_1") (pintype "input"))
    )
    (net (code "96") (name "TXD3") (class "Default")
      (node (ref "JP13") (pin "1") (pinfunction "1_1") (pintype "passive"))
      (node (ref "LPC1769") (pin "9") (pinfunction "9_9") (pintype "passive"))
    )
    (net (code "97") (name "USB_DM") (class "Default")
      (node (ref "LPC1769") (pin "36") (pinfunction "36_36") (pintype "passive"))
      (node (ref "U$2") (pin "D-") (pinfunction "D-_D-") (pintype "bidirectional"))
    )
    (net (code "98") (name "USB_DP") (class "Default")
      (node (ref "LPC1769") (pin "37") (pinfunction "37_37") (pintype "passive"))
      (node (ref "U$2") (pin "D+") (pinfunction "D+_D+") (pintype "bidirectional"))
    )
    (net (code "99") (name "unconnected-(J4-Pad1)") (class "Default")
      (node (ref "J4") (pin "1") (pinfunction "1_1") (pintype "passive"))
    )
    (net (code "100") (name "unconnected-(J4-Pad9)") (class "Default")
      (node (ref "J4") (pin "9") (pinfunction "9_9") (pintype "passive"))
    )
    (net (code "101") (name "unconnected-(JP2-Pad17)") (class "Default")
      (node (ref "JP2") (pin "17") (pinfunction "17_17") (pintype "passive"))
    )
    (net (code "102") (name "unconnected-(JP2-Pad21)") (class "Default")
      (node (ref "JP2") (pin "21") (pinfunction "21_21") (pintype "passive"))
    )
    (net (code "103") (name "unconnected-(LPC1769-Pad3)") (class "Default")
      (node (ref "LPC1769") (pin "3") (pinfunction "3_3") (pintype "passive"))
    )
    (net (code "104") (name "unconnected-(LPC1769-Pad4)") (class "Default")
      (node (ref "LPC1769") (pin "4") (pinfunction "4_4") (pintype "passive"))
    )
    (net (code "105") (name "unconnected-(LPC1769-Pad13)") (class "Default")
      (node (ref "LPC1769") (pin "13") (pinfunction "13_13") (pintype "passive"))
    )
    (net (code "106") (name "unconnected-(LPC1769-Pad19)") (class "Default")
      (node (ref "LPC1769") (pin "19") (pinfunction "19_19") (pintype "passive"))
    )
    (net (code "107") (name "unconnected-(LPC1769-Pad20)") (class "Default")
      (node (ref "LPC1769") (pin "20") (pinfunction "20_20") (pintype "passive"))
    )
    (net (code "108") (name "unconnected-(LPC1769-Pad27)") (class "Default")
      (node (ref "LPC1769") (pin "27") (pinfunction "27_27") (pintype "passive"))
    )
    (net (code "109") (name "unconnected-(LPC1769-Pad28)") (class "Default")
      (node (ref "LPC1769") (pin "28") (pinfunction "28_28") (pintype "passive"))
    )
    (net (code "110") (name "unconnected-(LPC1769-Pad29)") (class "Default")
      (node (ref "LPC1769") (pin "29") (pinfunction "29_29") (pintype "passive"))
    )
    (net (code "111") (name "unconnected-(LPC1769-Pad30)") (class "Default")
      (node (ref "LPC1769") (pin "30") (pinfunction "30_30") (pintype "passive"))
    )
    (net (code "112") (name "unconnected-(LPC1769-Pad31)") (class "Default")
      (node (ref "LPC1769") (pin "31") (pinfunction "31_31") (pintype "passive"))
    )
    (net (code "113") (name "unconnected-(LPC1769-Pad32)") (class "Default")
      (node (ref "LPC1769") (pin "32") (pinfunction "32_32") (pintype "passive"))
    )
    (net (code "114") (name "unconnected-(LPC1769-Pad33)") (class "Default")
      (node (ref "LPC1769") (pin "33") (pinfunction "33_33") (pintype "passive"))
    )
    (net (code "115") (name "unconnected-(LPC1769-Pad34)") (class "Default")
      (node (ref "LPC1769") (pin "34") (pinfunction "34_34") (pintype "passive"))
    )
    (net (code "116") (name "unconnected-(LPC1769-Pad35)") (class "Default")
      (node (ref "LPC1769") (pin "35") (pinfunction "35_35") (pintype "passive"))
    )
    (net (code "117") (name "unconnected-(LPC1769-Pad40)") (class "Default")
      (node (ref "LPC1769") (pin "40") (pinfunction "40_40") (pintype "passive"))
    )
    (net (code "118") (name "unconnected-(LPC1769-Pad41)") (class "Default")
      (node (ref "LPC1769") (pin "41") (pinfunction "41_41") (pintype "passive"))
    )
    (net (code "119") (name "unconnected-(LPC1769-Pad50)") (class "Default")
      (node (ref "LPC1769") (pin "50") (pinfunction "50_50") (pintype "passive"))
    )
    (net (code "120") (name "unconnected-(LPC1769-Pad51)") (class "Default")
      (node (ref "LPC1769") (pin "51") (pinfunction "51_51") (pintype "passive"))
    )
    (net (code "121") (name "unconnected-(LPC1769-Pad52)") (class "Default")
      (node (ref "LPC1769") (pin "52") (pinfunction "52_52") (pintype "passive"))
    )
    (net (code "122") (name "unconnected-(LPC1769-Pad53)") (class "Default")
      (node (ref "LPC1769") (pin "53") (pinfunction "53_53") (pintype "passive"))
    )
    (net (code "123") (name "unconnected-(LPC1769-Pad54)") (class "Default")
      (node (ref "LPC1769") (pin "54") (pinfunction "54_54") (pintype "passive"))
    )
    (net (code "124") (name "unconnected-(LPC1769-Pad55)") (class "Default")
      (node (ref "LPC1769") (pin "55") (pinfunction "55_55") (pintype "passive"))
    )
    (net (code "125") (name "unconnected-(LPC1769-Pad58)") (class "Default")
      (node (ref "LPC1769") (pin "58") (pinfunction "58_58") (pintype "passive"))
    )
    (net (code "126") (name "unconnected-(LPC1769-Pad59)") (class "Default")
      (node (ref "LPC1769") (pin "59") (pinfunction "59_59") (pintype "passive"))
    )
    (net (code "127") (name "unconnected-(LPC1769-Pad60)") (class "Default")
      (node (ref "LPC1769") (pin "60") (pinfunction "60_60") (pintype "passive"))
    )
    (net (code "128") (name "unconnected-(LPC1769-Pad61)") (class "Default")
      (node (ref "LPC1769") (pin "61") (pinfunction "61_61") (pintype "passive"))
    )
    (net (code "129") (name "unconnected-(LPC1769-Pad62)") (class "Default")
      (node (ref "LPC1769") (pin "62") (pinfunction "62_62") (pintype "passive"))
    )
    (net (code "130") (name "unconnected-(LPC1769-Pad63)") (class "Default")
      (node (ref "LPC1769") (pin "63") (pinfunction "63_63") (pintype "passive"))
    )
    (net (code "131") (name "unconnected-(LPC1769-Pad64)") (class "Default")
      (node (ref "LPC1769") (pin "64") (pinfunction "64_64") (pintype "passive"))
    )
    (net (code "132") (name "unconnected-(LPC1769-Pad65)") (class "Default")
      (node (ref "LPC1769") (pin "65") (pinfunction "65_65") (pintype "passive"))
    )
    (net (code "133") (name "unconnected-(LPC1769-Pad66)") (class "Default")
      (node (ref "LPC1769") (pin "66") (pinfunction "66_66") (pintype "passive"))
    )
    (net (code "134") (name "unconnected-(LPC1769-Pad67)") (class "Default")
      (node (ref "LPC1769") (pin "67") (pinfunction "67_67") (pintype "passive"))
    )
    (net (code "135") (name "unconnected-(LPC1769-Pad68)") (class "Default")
      (node (ref "LPC1769") (pin "68") (pinfunction "68_68") (pintype "passive"))
    )
    (net (code "136") (name "unconnected-(LPC1769-Pad69)") (class "Default")
      (node (ref "LPC1769") (pin "69") (pinfunction "69_69") (pintype "passive"))
    )
    (net (code "137") (name "unconnected-(LPC1769-Pad70)") (class "Default")
      (node (ref "LPC1769") (pin "70") (pinfunction "70_70") (pintype "passive"))
    )
    (net (code "138") (name "unconnected-(LPC1769-Pad71)") (class "Default")
      (node (ref "LPC1769") (pin "71") (pinfunction "71_71") (pintype "passive"))
    )
    (net (code "139") (name "unconnected-(LPC1769-Pad72)") (class "Default")
      (node (ref "LPC1769") (pin "72") (pinfunction "72_72") (pintype "passive"))
    )
    (net (code "140") (name "unconnected-(LPC1769-Pad73)") (class "Default")
      (node (ref "LPC1769") (pin "73") (pinfunction "73_73") (pintype "passive"))
    )
    (net (code "141") (name "unconnected-(U$2-PadID)") (class "Default")
      (node (ref "U$2") (pin "ID") (pinfunction "ID_ID") (pintype "bidirectional"))
    )
    (net (code "142") (name "unconnected-(U8-R1IN-Pad4)") (class "Default")
      (node (ref "U8") (pin "4") (pinfunction "R1IN_4") (pintype "input"))
    )
    (net (code "143") (name "unconnected-(U8-R1OUT-Pad3)") (class "Default")
      (node (ref "U8") (pin "3") (pinfunction "R1OUT_3") (pintype "output"))
    )
    (net (code "144") (name "unconnected-(U8-T1IN-Pad2)") (class "Default")
      (node (ref "U8") (pin "2") (pinfunction "T1IN_2") (pintype "input"))
    )
    (net (code "145") (name "unconnected-(U8-T1OUT-Pad5)") (class "Default")
      (node (ref "U8") (pin "5") (pinfunction "T1OUT_5") (pintype "output"))
    )
  )
)
